# core-feather-shield-adc-imu-advanced_v1_.net
KiCad netlist of a schematic drawn in EAGLE
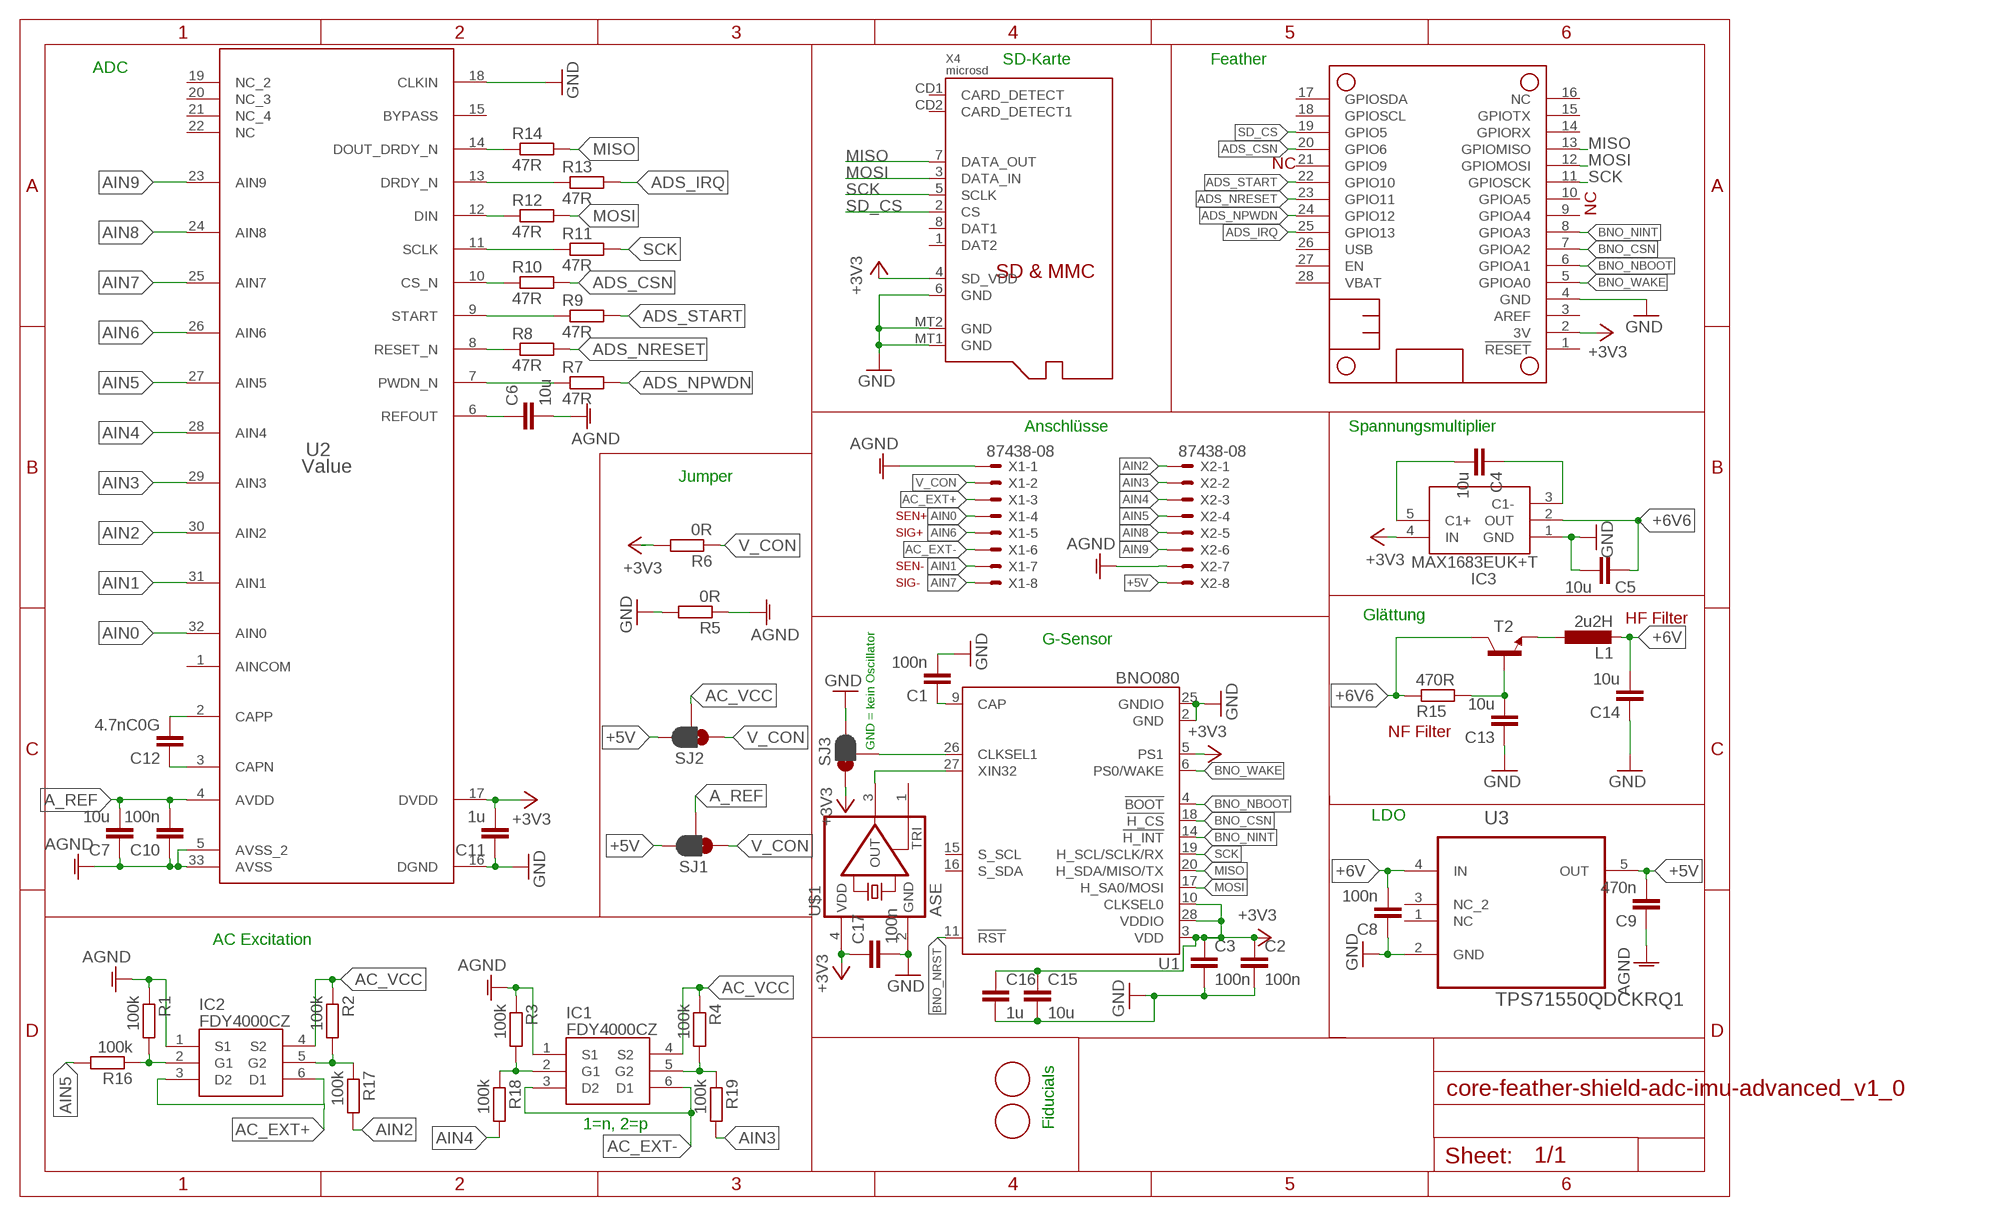
[diagram p0: schematic, sheet 1]

(export (version "E")
  (design (tool "Eeschema 10.0.6"))
  (components
    (comp (ref "C1")
      (value "100n")
      (footprint "eagle-import:C0805")
      (libsource (lib "eagle-import") (part "C-EUC0805"))
    )
    (comp (ref "C2")
      (value "100n")
      (footprint "eagle-import:C0805")
      (libsource (lib "eagle-import") (part "C-EUC0805"))
    )
    (comp (ref "C3")
      (value "100n")
      (footprint "eagle-import:C0805")
      (libsource (lib "eagle-import") (part "C-EUC0805"))
    )
    (comp (ref "C4")
      (value "10u")
      (footprint "eagle-import:C0805")
      (libsource (lib "eagle-import") (part "C-EUC0805"))
    )
    (comp (ref "C5")
      (value "10u")
      (footprint "eagle-import:C0805")
      (libsource (lib "eagle-import") (part "C-EUC0805"))
    )
    (comp (ref "C6")
      (value "10u")
      (footprint "eagle-import:C0805")
      (libsource (lib "eagle-import") (part "C-EUC0805"))
    )
    (comp (ref "C7")
      (value "10u")
      (footprint "eagle-import:C0805")
      (libsource (lib "eagle-import") (part "C-EUC0805"))
    )
    (comp (ref "C8")
      (value "100n")
      (footprint "eagle-import:C0805")
      (libsource (lib "eagle-import") (part "C-EUC0805"))
    )
    (comp (ref "C9")
      (value "470n")
      (footprint "eagle-import:C0805")
      (libsource (lib "eagle-import") (part "C-EUC0805"))
    )
    (comp (ref "C10")
      (value "100n")
      (footprint "eagle-import:C0805")
      (libsource (lib "eagle-import") (part "C-EUC0805"))
    )
    (comp (ref "C11")
      (value "1u")
      (footprint "eagle-import:C0805")
      (libsource (lib "eagle-import") (part "C-EUC0805"))
    )
    (comp (ref "C12")
      (value "4.7nC0G")
      (footprint "eagle-import:C0805")
      (libsource (lib "eagle-import") (part "C-EUC0805"))
    )
    (comp (ref "C13")
      (value "10u")
      (footprint "eagle-import:C0805")
      (libsource (lib "eagle-import") (part "C-EUC0805"))
    )
    (comp (ref "C14")
      (value "10u")
      (footprint "eagle-import:C0805")
      (libsource (lib "eagle-import") (part "C-EUC0805"))
    )
    (comp (ref "C15")
      (value "10u")
      (footprint "eagle-import:C0805")
      (libsource (lib "eagle-import") (part "C-EUC0805"))
    )
    (comp (ref "C16")
      (value "1u")
      (footprint "eagle-import:C0805")
      (libsource (lib "eagle-import") (part "C-EUC0805"))
    )
    (comp (ref "C17")
      (value "100n")
      (footprint "eagle-import:C0805")
      (libsource (lib "eagle-import") (part "C-EUC0805"))
    )
    (comp (ref "IC1")
      (value "FDY4000CZ")
      (footprint "eagle-import:SOTFL50P160X60-6N")
      (fields (field (name "MOUSER_PART_NUMBER") "512-FDY4000CZ") (field (name "RS_PART_NUMBER") "6710857"))
      (libsource (lib "eagle-import") (part "FDY4000CZ"))
    )
    (comp (ref "IC2")
      (value "FDY4000CZ")
      (footprint "eagle-import:SOTFL50P160X60-6N")
      (fields (field (name "MOUSER_PART_NUMBER") "512-FDY4000CZ") (field (name "RS_PART_NUMBER") "6710857"))
      (libsource (lib "eagle-import") (part "FDY4000CZ"))
    )
    (comp (ref "IC3")
      (value "MAX1683EUK+T")
      (footprint "eagle-import:SOT95P280X145-5N")
      (fields (field (name "MOUSER_PART_NUMBER") "700-MAX1683EUKT"))
      (libsource (lib "eagle-import") (part "MAX1683EUK+T"))
    )
    (comp (ref "L1")
      (value "2u2H")
      (footprint "eagle-import:L0805")
      (libsource (lib "eagle-import") (part "L-EUL0805"))
    )
    (comp (ref "MS1")
      (value "FEATHERWING")
      (footprint "eagle-import:FEATHERWING")
      (libsource (lib "eagle-import") (part "FEATHERWING"))
    )
    (comp (ref "R1")
      (value "100k")
      (footprint "eagle-import:R0805")
      (libsource (lib "eagle-import") (part "R-EU_R0805"))
    )
    (comp (ref "R2")
      (value "100k")
      (footprint "eagle-import:R0805")
      (libsource (lib "eagle-import") (part "R-EU_R0805"))
    )
    (comp (ref "R3")
      (value "100k")
      (footprint "eagle-import:R0805")
      (libsource (lib "eagle-import") (part "R-EU_R0805"))
    )
    (comp (ref "R4")
      (value "100k")
      (footprint "eagle-import:R0805")
      (libsource (lib "eagle-import") (part "R-EU_R0805"))
    )
    (comp (ref "R5")
      (value "0R")
      (footprint "eagle-import:R0805")
      (libsource (lib "eagle-import") (part "R-EU_R0805"))
    )
    (comp (ref "R6")
      (value "0R")
      (footprint "eagle-import:R0805")
      (libsource (lib "eagle-import") (part "R-EU_R0805"))
    )
    (comp (ref "R7")
      (value "47R")
      (footprint "eagle-import:R0805")
      (libsource (lib "eagle-import") (part "R-EU_R0805"))
    )
    (comp (ref "R8")
      (value "47R")
      (footprint "eagle-import:R0805")
      (libsource (lib "eagle-import") (part "R-EU_R0805"))
    )
    (comp (ref "R9")
      (value "47R")
      (footprint "eagle-import:R0805")
      (libsource (lib "eagle-import") (part "R-EU_R0805"))
    )
    (comp (ref "R10")
      (value "47R")
      (footprint "eagle-import:R0805")
      (libsource (lib "eagle-import") (part "R-EU_R0805"))
    )
    (comp (ref "R11")
      (value "47R")
      (footprint "eagle-import:R0805")
      (libsource (lib "eagle-import") (part "R-EU_R0805"))
    )
    (comp (ref "R12")
      (value "47R")
      (footprint "eagle-import:R0805")
      (libsource (lib "eagle-import") (part "R-EU_R0805"))
    )
    (comp (ref "R13")
      (value "47R")
      (footprint "eagle-import:R0805")
      (libsource (lib "eagle-import") (part "R-EU_R0805"))
    )
    (comp (ref "R14")
      (value "47R")
      (footprint "eagle-import:R0805")
      (libsource (lib "eagle-import") (part "R-EU_R0805"))
    )
    (comp (ref "R15")
      (value "470R")
      (footprint "eagle-import:R0805")
      (libsource (lib "eagle-import") (part "R-EU_R0805"))
    )
    (comp (ref "R16")
      (value "100k")
      (footprint "eagle-import:R0805")
      (libsource (lib "eagle-import") (part "R-EU_R0805"))
    )
    (comp (ref "R17")
      (value "100k")
      (footprint "eagle-import:R0805")
      (libsource (lib "eagle-import") (part "R-EU_R0805"))
    )
    (comp (ref "R18")
      (value "100k")
      (footprint "eagle-import:R0805")
      (libsource (lib "eagle-import") (part "R-EU_R0805"))
    )
    (comp (ref "R19")
      (value "100k")
      (footprint "eagle-import:R0805")
      (libsource (lib "eagle-import") (part "R-EU_R0805"))
    )
    (comp (ref "SJ1")
      (value "JUMPER_PAD-3-1&2_NC_BY_PASTE")
      (footprint "eagle-import:PAD-HUMPER-3-1&2_NC_BY_PASTE_YES_SILK_FULL_BOX")
      (libsource (lib "eagle-import") (part "JUMPER_PAD-3-1&2_NC_BY_PASTE"))
    )
    (comp (ref "SJ2")
      (value "JUMPER_PAD-3-1&2_NC_BY_PASTE")
      (footprint "eagle-import:PAD-HUMPER-3-1&2_NC_BY_PASTE_YES_SILK_FULL_BOX")
      (libsource (lib "eagle-import") (part "JUMPER_PAD-3-1&2_NC_BY_PASTE"))
    )
    (comp (ref "SJ3")
      (value "JUMPER_PAD-3-1&2_NC_BY_PASTE")
      (footprint "eagle-import:PAD-HUMPER-3-1&2_NC_BY_PASTE_YES_SILK_FULL_BOX")
      (libsource (lib "eagle-import") (part "JUMPER_PAD-3-1&2_NC_BY_PASTE"))
    )
    (comp (ref "T2")
      (value "BC808-NPN-SOT23-BEC")
      (footprint "eagle-import:SOT23-BEC")
      (libsource (lib "eagle-import") (part "-NPN-SOT23-BECBC808"))
    )
    (comp (ref "U$1")
      (value "ASE")
      (footprint "eagle-import:ASE")
      (libsource (lib "eagle-import") (part "ASE"))
    )
    (comp (ref "U$8")
      (value "FIDUCIAL")
      (footprint "eagle-import:FIDUCIAL_1MM")
      (libsource (lib "eagle-import") (part "FIDUCIAL"))
    )
    (comp (ref "U$9")
      (value "FIDUCIAL")
      (footprint "eagle-import:FIDUCIAL_1MM")
      (libsource (lib "eagle-import") (part "FIDUCIAL"))
    )
    (comp (ref "U1")
      (value "BNO080")
      (footprint "eagle-import:LGA-28")
      (fields (field (name "MF") "Hillcrest Laboratories,"))
      (libsource (lib "eagle-import") (part "BNO080"))
    )
    (comp (ref "U2")
      (value "Value")
      (footprint "eagle-import:RHB0032E")
      (fields (field (name "MANUFACTURER") "Texas Instruments") (field (name "PARTNUMBER") "ADS1261IRHBR"))
      (libsource (lib "eagle-import") (part "ADS1261IRHBR"))
    )
    (comp (ref "U3")
      (value "TPS71550QDCKRQ1")
      (footprint "eagle-import:SOT65P210X110-5N")
      (fields (field (name "MF") "Texas Instruments"))
      (libsource (lib "eagle-import") (part "TPS71550QDCKRQ1"))
    )
    (comp (ref "X1")
      (value "87438-08")
      (footprint "eagle-import:87438-08")
      (fields (field (name "MF") "MOLEX") (field (name "SPICEPREFIX") "X"))
      (libsource (lib "eagle-import") (part "87438-08"))
    )
    (comp (ref "X2")
      (value "87438-08")
      (footprint "eagle-import:87438-08")
      (fields (field (name "MF") "MOLEX") (field (name "SPICEPREFIX") "X"))
      (libsource (lib "eagle-import") (part "87438-08"))
    )
    (comp (ref "X4")
      (value "microsd")
      (footprint "eagle-import:MICROSD")
      (libsource (lib "eagle-import") (part "MICROSD"))
    )
  )
  (nets
    (net (code "1") (name "+3V3") (class "Default")
      (node (ref "C11") (pin "2") (pinfunction "2_2") (pintype "passive"))
      (node (ref "C15") (pin "1") (pinfunction "1_1") (pintype "passive"))
      (node (ref "C16") (pin "1") (pinfunction "1_1") (pintype "passive"))
      (node (ref "C17") (pin "1") (pinfunction "1_1") (pintype "passive"))
      (node (ref "C2") (pin "1") (pinfunction "1_1") (pintype "passive"))
      (node (ref "C3") (pin "1") (pinfunction "1_1") (pintype "passive"))
      (node (ref "IC3") (pin "4") (pinfunction "IN_4") (pintype "input"))
      (node (ref "MS1") (pin "2") (pinfunction "3V_2") (pintype "power_in"))
      (node (ref "R6") (pin "2") (pinfunction "2_2") (pintype "passive"))
      (node (ref "SJ3") (pin "3") (pinfunction "3_3") (pintype "passive"))
      (node (ref "U$1") (pin "4") (pinfunction "VDD_4") (pintype "power_in"))
      (node (ref "U1") (pin "10") (pinfunction "CLKSEL0_10") (pintype "bidirectional"))
      (node (ref "U1") (pin "28") (pinfunction "VDDIO_28") (pintype "bidirectional"))
      (node (ref "U1") (pin "3") (pinfunction "VDD_3") (pintype "bidirectional"))
      (node (ref "U1") (pin "5") (pinfunction "PS1_5") (pintype "bidirectional"))
      (node (ref "U2") (pin "17") (pinfunction "DVDD_17") (pintype "power_in"))
      (node (ref "X4") (pin "4") (pinfunction "SD_VDD_4") (pintype "power_in"))
    )
    (net (code "2") (name "+5V") (class "Default")
      (node (ref "C9") (pin "2") (pinfunction "2_2") (pintype "passive"))
      (node (ref "SJ1") (pin "1") (pinfunction "1_1") (pintype "passive"))
      (node (ref "SJ2") (pin "1") (pinfunction "1_1") (pintype "passive"))
      (node (ref "U3") (pin "5") (pinfunction "OUT_5") (pintype "output"))
      (node (ref "X2") (pin "8") (pinfunction "S_8") (pintype "passive"))
    )
    (net (code "3") (name "+6V") (class "Default")
      (node (ref "C14") (pin "2") (pinfunction "2_2") (pintype "passive"))
      (node (ref "C8") (pin "2") (pinfunction "2_2") (pintype "passive"))
      (node (ref "L1") (pin "2") (pinfunction "2_2") (pintype "passive"))
      (node (ref "U3") (pin "4") (pinfunction "IN_4") (pintype "power_in"))
    )
    (net (code "4") (name "+6V6") (class "Default")
      (node (ref "C5") (pin "1") (pinfunction "1_1") (pintype "passive"))
      (node (ref "IC3") (pin "2") (pinfunction "OUT_2") (pintype "output"))
      (node (ref "R15") (pin "2") (pinfunction "2_2") (pintype "passive"))
      (node (ref "T2") (pin "C") (pinfunction "C_C") (pintype "passive"))
    )
    (net (code "5") (name "/USB") (class "Default")
      (node (ref "MS1") (pin "26") (pinfunction "USB_26") (pintype "power_in"))
    )
    (net (code "6") (name "/VBAT") (class "Default")
      (node (ref "MS1") (pin "28") (pinfunction "VBAT_28") (pintype "power_in"))
    )
    (net (code "7") (name "AC_EXT+") (class "Default")
      (node (ref "IC2") (pin "3") (pinfunction "D2_3") (pintype "bidirectional"))
      (node (ref "IC2") (pin "6") (pinfunction "D1_6") (pintype "bidirectional"))
      (node (ref "X1") (pin "3") (pinfunction "S_3") (pintype "passive"))
    )
    (net (code "8") (name "AC_EXT-") (class "Default")
      (node (ref "IC1") (pin "3") (pinfunction "D2_3") (pintype "bidirectional"))
      (node (ref "IC1") (pin "6") (pinfunction "D1_6") (pintype "bidirectional"))
      (node (ref "X1") (pin "6") (pinfunction "S_6") (pintype "passive"))
    )
    (net (code "9") (name "AC_VCC") (class "Default")
      (node (ref "IC1") (pin "4") (pinfunction "S2_4") (pintype "bidirectional"))
      (node (ref "IC2") (pin "4") (pinfunction "S2_4") (pintype "bidirectional"))
      (node (ref "R2") (pin "1") (pinfunction "1_1") (pintype "passive"))
      (node (ref "R4") (pin "1") (pinfunction "1_1") (pintype "passive"))
      (node (ref "SJ2") (pin "2") (pinfunction "2_2") (pintype "passive"))
    )
    (net (code "10") (name "ADS_CSN") (class "Default")
      (node (ref "MS1") (pin "20") (pinfunction "GPIO6_20") (pintype "bidirectional"))
      (node (ref "R10") (pin "2") (pinfunction "2_2") (pintype "passive"))
    )
    (net (code "11") (name "ADS_IRQ") (class "Default")
      (node (ref "MS1") (pin "25") (pinfunction "GPIO13_25") (pintype "bidirectional"))
      (node (ref "R13") (pin "2") (pinfunction "2_2") (pintype "passive"))
    )
    (net (code "12") (name "ADS_NPWDN") (class "Default")
      (node (ref "MS1") (pin "24") (pinfunction "GPIO12_24") (pintype "bidirectional"))
      (node (ref "R7") (pin "2") (pinfunction "2_2") (pintype "passive"))
    )
    (net (code "13") (name "ADS_NRESET") (class "Default")
      (node (ref "MS1") (pin "23") (pinfunction "GPIO11_23") (pintype "bidirectional"))
      (node (ref "R8") (pin "2") (pinfunction "2_2") (pintype "passive"))
    )
    (net (code "14") (name "ADS_START") (class "Default")
      (node (ref "MS1") (pin "22") (pinfunction "GPIO10_22") (pintype "bidirectional"))
      (node (ref "R9") (pin "2") (pinfunction "2_2") (pintype "passive"))
    )
    (net (code "15") (name "AGND") (class "Default")
      (node (ref "C10") (pin "1") (pinfunction "1_1") (pintype "passive"))
      (node (ref "C6") (pin "2") (pinfunction "2_2") (pintype "passive"))
      (node (ref "C7") (pin "1") (pinfunction "1_1") (pintype "passive"))
      (node (ref "C9") (pin "1") (pinfunction "1_1") (pintype "passive"))
      (node (ref "IC1") (pin "1") (pinfunction "S1_1") (pintype "bidirectional"))
      (node (ref "IC2") (pin "1") (pinfunction "S1_1") (pintype "bidirectional"))
      (node (ref "R1") (pin "1") (pinfunction "1_1") (pintype "passive"))
      (node (ref "R3") (pin "1") (pinfunction "1_1") (pintype "passive"))
      (node (ref "R5") (pin "1") (pinfunction "1_1") (pintype "passive"))
      (node (ref "U2") (pin "33") (pinfunction "AVSS_33") (pintype "power_in"))
      (node (ref "U2") (pin "5") (pinfunction "AVSS_2_5") (pintype "power_in"))
      (node (ref "X1") (pin "1") (pinfunction "S_1") (pintype "passive"))
      (node (ref "X2") (pin "7") (pinfunction "S_7") (pintype "passive"))
    )
    (net (code "16") (name "AIN0") (class "Default")
      (node (ref "U2") (pin "32") (pinfunction "AIN0_32") (pintype "input"))
      (node (ref "X1") (pin "4") (pinfunction "S_4") (pintype "passive"))
    )
    (net (code "17") (name "AIN1") (class "Default")
      (node (ref "U2") (pin "31") (pinfunction "AIN1_31") (pintype "input"))
      (node (ref "X1") (pin "7") (pinfunction "S_7") (pintype "passive"))
    )
    (net (code "18") (name "AIN2") (class "Default")
      (node (ref "R17") (pin "2") (pinfunction "2_2") (pintype "passive"))
      (node (ref "U2") (pin "30") (pinfunction "AIN2_30") (pintype "input"))
      (node (ref "X2") (pin "1") (pinfunction "S_1") (pintype "passive"))
    )
    (net (code "19") (name "AIN3") (class "Default")
      (node (ref "R19") (pin "2") (pinfunction "2_2") (pintype "passive"))
      (node (ref "U2") (pin "29") (pinfunction "AIN3_29") (pintype "input"))
      (node (ref "X2") (pin "2") (pinfunction "S_2") (pintype "passive"))
    )
    (net (code "20") (name "AIN4") (class "Default")
      (node (ref "R18") (pin "2") (pinfunction "2_2") (pintype "passive"))
      (node (ref "U2") (pin "28") (pinfunction "AIN4_28") (pintype "input"))
      (node (ref "X2") (pin "3") (pinfunction "S_3") (pintype "passive"))
    )
    (net (code "21") (name "AIN5") (class "Default")
      (node (ref "R16") (pin "2") (pinfunction "2_2") (pintype "passive"))
      (node (ref "U2") (pin "27") (pinfunction "AIN5_27") (pintype "input"))
      (node (ref "X2") (pin "4") (pinfunction "S_4") (pintype "passive"))
    )
    (net (code "22") (name "AIN6") (class "Default")
      (node (ref "U2") (pin "26") (pinfunction "AIN6_26") (pintype "input"))
      (node (ref "X1") (pin "5") (pinfunction "S_5") (pintype "passive"))
    )
    (net (code "23") (name "AIN7") (class "Default")
      (node (ref "U2") (pin "25") (pinfunction "AIN7_25") (pintype "input"))
      (node (ref "X1") (pin "8") (pinfunction "S_8") (pintype "passive"))
    )
    (net (code "24") (name "AIN8") (class "Default")
      (node (ref "U2") (pin "24") (pinfunction "AIN8_24") (pintype "input"))
      (node (ref "X2") (pin "5") (pinfunction "S_5") (pintype "passive"))
    )
    (net (code "25") (name "AIN9") (class "Default")
      (node (ref "U2") (pin "23") (pinfunction "AIN9_23") (pintype "input"))
      (node (ref "X2") (pin "6") (pinfunction "S_6") (pintype "passive"))
    )
    (net (code "26") (name "A_REF") (class "Default")
      (node (ref "C10") (pin "2") (pinfunction "2_2") (pintype "passive"))
      (node (ref "C7") (pin "2") (pinfunction "2_2") (pintype "passive"))
      (node (ref "SJ1") (pin "2") (pinfunction "2_2") (pintype "passive"))
      (node (ref "U2") (pin "4") (pinfunction "AVDD_4") (pintype "power_in"))
    )
    (net (code "27") (name "BNO_CSN") (class "Default")
      (node (ref "MS1") (pin "7") (pinfunction "GPIOA2_7") (pintype "bidirectional"))
      (node (ref "U1") (pin "18") (pinfunction "~{H_CS}_18") (pintype "bidirectional"))
    )
    (net (code "28") (name "BNO_NBOOT") (class "Default")
      (node (ref "MS1") (pin "6") (pinfunction "GPIOA1_6") (pintype "bidirectional"))
      (node (ref "U1") (pin "4") (pinfunction "~{BOOT}_4") (pintype "bidirectional"))
    )
    (net (code "29") (name "BNO_NINT") (class "Default")
      (node (ref "MS1") (pin "8") (pinfunction "GPIOA3_8") (pintype "bidirectional"))
      (node (ref "U1") (pin "14") (pinfunction "~{H_INT}_14") (pintype "bidirectional"))
    )
    (net (code "30") (name "BNO_NRST") (class "Default")
      (node (ref "U1") (pin "11") (pinfunction "~{RST}_11") (pintype "bidirectional"))
    )
    (net (code "31") (name "BNO_WAKE") (class "Default")
      (node (ref "MS1") (pin "5") (pinfunction "GPIOA0_5") (pintype "bidirectional"))
      (node (ref "U1") (pin "6") (pinfunction "PS0/WAKE_6") (pintype "bidirectional"))
    )
    (net (code "32") (name "GND") (class "Default")
      (node (ref "C1") (pin "2") (pinfunction "2_2") (pintype "passive"))
      (node (ref "C11") (pin "1") (pinfunction "1_1") (pintype "passive"))
      (node (ref "C13") (pin "1") (pinfunction "1_1") (pintype "passive"))
      (node (ref "C14") (pin "1") (pinfunction "1_1") (pintype "passive"))
      (node (ref "C15") (pin "2") (pinfunction "2_2") (pintype "passive"))
      (node (ref "C16") (pin "2") (pinfunction "2_2") (pintype "passive"))
      (node (ref "C17") (pin "2") (pinfunction "2_2") (pintype "passive"))
      (node (ref "C2") (pin "2") (pinfunction "2_2") (pintype "passive"))
      (node (ref "C3") (pin "2") (pinfunction "2_2") (pintype "passive"))
      (node (ref "C5") (pin "2") (pinfunction "2_2") (pintype "passive"))
      (node (ref "C8") (pin "1") (pinfunction "1_1") (pintype "passive"))
      (node (ref "IC3") (pin "1") (pinfunction "GND_1") (pintype "power_in"))
      (node (ref "MS1") (pin "4") (pinfunction "GND_4") (pintype "power_in"))
      (node (ref "R5") (pin "2") (pinfunction "2_2") (pintype "passive"))
      (node (ref "SJ3") (pin "1") (pinfunction "1_1") (pintype "passive"))
      (node (ref "U$1") (pin "2") (pinfunction "GND_2") (pintype "power_in"))
      (node (ref "U1") (pin "2") (pinfunction "GND_2") (pintype "bidirectional"))
      (node (ref "U1") (pin "25") (pinfunction "GNDIO_25") (pintype "bidirectional"))
      (node (ref "U2") (pin "16") (pinfunction "DGND_16") (pintype "power_in"))
      (node (ref "U2") (pin "18") (pinfunction "CLKIN_18") (pintype "input"))
      (node (ref "U3") (pin "2") (pinfunction "GND_2") (pintype "passive"))
      (node (ref "X4") (pin "6") (pinfunction "GND_6") (pintype "power_in"))
      (node (ref "X4") (pin "MT1") (pinfunction "GND_MT1") (pintype "power_in"))
      (node (ref "X4") (pin "MT2") (pinfunction "GND_MT2") (pintype "power_in"))
    )
    (net (code "33") (name "MISO") (class "Default")
      (node (ref "MS1") (pin "13") (pinfunction "GPIOMISO_13") (pintype "bidirectional"))
      (node (ref "R14") (pin "2") (pinfunction "2_2") (pintype "passive"))
      (node (ref "U1") (pin "20") (pinfunction "H_SDA/MISO/TX_20") (pintype "bidirectional"))
      (node (ref "X4") (pin "7") (pinfunction "DATA_OUT_7") (pintype "output"))
    )
    (net (code "34") (name "MOSI") (class "Default")
      (node (ref "MS1") (pin "12") (pinfunction "GPIOMOSI_12") (pintype "bidirectional"))
      (node (ref "R12") (pin "2") (pinfunction "2_2") (pintype "passive"))
      (node (ref "U1") (pin "17") (pinfunction "H_SA0/MOSI_17") (pintype "bidirectional"))
      (node (ref "X4") (pin "3") (pinfunction "DATA_IN_3") (pintype "input"))
    )
    (net (code "35") (name "Net-(C13-Pad2)") (class "Default")
      (node (ref "C13") (pin "2") (pinfunction "2_2") (pintype "passive"))
      (node (ref "R15") (pin "1") (pinfunction "1_1") (pintype "passive"))
      (node (ref "T2") (pin "B") (pinfunction "B_B") (pintype "passive"))
    )
    (net (code "36") (name "Net-(IC1-G1)") (class "Default")
      (node (ref "IC1") (pin "2") (pinfunction "G1_2") (pintype "bidirectional"))
      (node (ref "R18") (pin "1") (pinfunction "1_1") (pintype "passive"))
      (node (ref "R3") (pin "2") (pinfunction "2_2") (pintype "passive"))
    )
    (net (code "37") (name "Net-(IC1-G2)") (class "Default")
      (node (ref "IC1") (pin "5") (pinfunction "G2_5") (pintype "bidirectional"))
      (node (ref "R19") (pin "1") (pinfunction "1_1") (pintype "passive"))
      (node (ref "R4") (pin "2") (pinfunction "2_2") (pintype "passive"))
    )
    (net (code "38") (name "Net-(IC2-G1)") (class "Default")
      (node (ref "IC2") (pin "2") (pinfunction "G1_2") (pintype "bidirectional"))
      (node (ref "R1") (pin "2") (pinfunction "2_2") (pintype "passive"))
      (node (ref "R16") (pin "1") (pinfunction "1_1") (pintype "passive"))
    )
    (net (code "39") (name "Net-(IC2-G2)") (class "Default")
      (node (ref "IC2") (pin "5") (pinfunction "G2_5") (pintype "bidirectional"))
      (node (ref "R17") (pin "1") (pinfunction "1_1") (pintype "passive"))
      (node (ref "R2") (pin "2") (pinfunction "2_2") (pintype "passive"))
    )
    (net (code "40") (name "Net-(IC3-C1+)") (class "Default")
      (node (ref "C4") (pin "2") (pinfunction "2_2") (pintype "passive"))
      (node (ref "IC3") (pin "5") (pinfunction "C1+_5") (pintype "bidirectional"))
    )
    (net (code "41") (name "Net-(IC3-C1-)") (class "Default")
      (node (ref "C4") (pin "1") (pinfunction "1_1") (pintype "passive"))
      (node (ref "IC3") (pin "3") (pinfunction "C1-_3") (pintype "bidirectional"))
    )
    (net (code "42") (name "Net-(L1-Pad1)") (class "Default")
      (node (ref "L1") (pin "1") (pinfunction "1_1") (pintype "passive"))
      (node (ref "T2") (pin "E") (pinfunction "E_E") (pintype "passive"))
    )
    (net (code "43") (name "Net-(U$1-OUT)") (class "Default")
      (node (ref "U$1") (pin "3") (pinfunction "OUT_3") (pintype "output"))
      (node (ref "U1") (pin "27") (pinfunction "XIN32_27") (pintype "bidirectional"))
    )
    (net (code "44") (name "Net-(U1-CAP)") (class "Default")
      (node (ref "C1") (pin "1") (pinfunction "1_1") (pintype "passive"))
      (node (ref "U1") (pin "9") (pinfunction "CAP_9") (pintype "bidirectional"))
    )
    (net (code "45") (name "Net-(U1-CLKSEL1)") (class "Default")
      (node (ref "SJ3") (pin "2") (pinfunction "2_2") (pintype "passive"))
      (node (ref "U1") (pin "26") (pinfunction "CLKSEL1_26") (pintype "bidirectional"))
    )
    (net (code "46") (name "Net-(U2-CAPN)") (class "Default")
      (node (ref "C12") (pin "1") (pinfunction "1_1") (pintype "passive"))
      (node (ref "U2") (pin "3") (pinfunction "CAPN_3") (pintype "passive"))
    )
    (net (code "47") (name "Net-(U2-CAPP)") (class "Default")
      (node (ref "C12") (pin "2") (pinfunction "2_2") (pintype "passive"))
      (node (ref "U2") (pin "2") (pinfunction "CAPP_2") (pintype "passive"))
    )
    (net (code "48") (name "Net-(U2-CS_N)") (class "Default")
      (node (ref "R10") (pin "1") (pinfunction "1_1") (pintype "passive"))
      (node (ref "U2") (pin "10") (pinfunction "CS_N_10") (pintype "input"))
    )
    (net (code "49") (name "Net-(U2-DIN)") (class "Default")
      (node (ref "R12") (pin "1") (pinfunction "1_1") (pintype "passive"))
      (node (ref "U2") (pin "12") (pinfunction "DIN_12") (pintype "input"))
    )
    (net (code "50") (name "Net-(U2-DOUT_DRDY_N)") (class "Default")
      (node (ref "R14") (pin "1") (pinfunction "1_1") (pintype "passive"))
      (node (ref "U2") (pin "14") (pinfunction "DOUT_DRDY_N_14") (pintype "output"))
    )
    (net (code "51") (name "Net-(U2-DRDY_N)") (class "Default")
      (node (ref "R13") (pin "1") (pinfunction "1_1") (pintype "passive"))
      (node (ref "U2") (pin "13") (pinfunction "DRDY_N_13") (pintype "output"))
    )
    (net (code "52") (name "Net-(U2-PWDN_N)") (class "Default")
      (node (ref "R7") (pin "1") (pinfunction "1_1") (pintype "passive"))
      (node (ref "U2") (pin "7") (pinfunction "PWDN_N_7") (pintype "input"))
    )
    (net (code "53") (name "Net-(U2-REFOUT)") (class "Default")
      (node (ref "C6") (pin "1") (pinfunction "1_1") (pintype "passive"))
      (node (ref "U2") (pin "6") (pinfunction "REFOUT_6") (pintype "output"))
    )
    (net (code "54") (name "Net-(U2-RESET_N)") (class "Default")
      (node (ref "R8") (pin "1") (pinfunction "1_1") (pintype "passive"))
      (node (ref "U2") (pin "8") (pinfunction "RESET_N_8") (pintype "input"))
    )
    (net (code "55") (name "Net-(U2-SCLK)") (class "Default")
      (node (ref "R11") (pin "1") (pinfunction "1_1") (pintype "passive"))
      (node (ref "U2") (pin "11") (pinfunction "SCLK_11") (pintype "input"))
    )
    (net (code "56") (name "Net-(U2-START)") (class "Default")
      (node (ref "R9") (pin "1") (pinfunction "1_1") (pintype "passive"))
      (node (ref "U2") (pin "9") (pinfunction "START_9") (pintype "input"))
    )
    (net (code "57") (name "SCK") (class "Default")
      (node (ref "MS1") (pin "11") (pinfunction "GPIOSCK_11") (pintype "bidirectional"))
      (node (ref "R11") (pin "2") (pinfunction "2_2") (pintype "passive"))
      (node (ref "U1") (pin "19") (pinfunction "H_SCL/SCLK/RX_19") (pintype "bidirectional"))
      (node (ref "X4") (pin "5") (pinfunction "SCLK_5") (pintype "input"))
    )
    (net (code "58") (name "SD_CS") (class "Default")
      (node (ref "MS1") (pin "19") (pinfunction "GPIO5_19") (pintype "bidirectional"))
      (node (ref "X4") (pin "2") (pinfunction "CS_2") (pintype "input"))
    )
    (net (code "59") (name "V_CON") (class "Default")
      (node (ref "R6") (pin "1") (pinfunction "1_1") (pintype "passive"))
      (node (ref "SJ1") (pin "3") (pinfunction "3_3") (pintype "passive"))
      (node (ref "SJ2") (pin "3") (pinfunction "3_3") (pintype "passive"))
      (node (ref "X1") (pin "2") (pinfunction "S_2") (pintype "passive"))
    )
    (net (code "60") (name "unconnected-(MS1-AREF-Pad3)") (class "Default")
      (node (ref "MS1") (pin "3") (pinfunction "AREF_3") (pintype "passive"))
    )
    (net (code "61") (name "unconnected-(MS1-EN-Pad27)") (class "Default")
      (node (ref "MS1") (pin "27") (pinfunction "EN_27") (pintype "passive"))
    )
    (net (code "62") (name "unconnected-(MS1-GPIO9-Pad21)") (class "Default")
      (node (ref "MS1") (pin "21") (pinfunction "GPIO9_21") (pintype "bidirectional"))
    )
    (net (code "63") (name "unconnected-(MS1-GPIOA4-Pad9)") (class "Default")
      (node (ref "MS1") (pin "9") (pinfunction "GPIOA4_9") (pintype "bidirectional"))
    )
    (net (code "64") (name "unconnected-(MS1-GPIOA5-Pad10)") (class "Default")
      (node (ref "MS1") (pin "10") (pinfunction "GPIOA5_10") (pintype "bidirectional"))
    )
    (net (code "65") (name "unconnected-(MS1-GPIORX-Pad14)") (class "Default")
      (node (ref "MS1") (pin "14") (pinfunction "GPIORX_14") (pintype "bidirectional"))
    )
    (net (code "66") (name "unconnected-(MS1-GPIOSCL-Pad18)") (class "Default")
      (node (ref "MS1") (pin "18") (pinfunction "GPIOSCL_18") (pintype "bidirectional"))
    )
    (net (code "67") (name "unconnected-(MS1-GPIOSDA-Pad17)") (class "Default")
      (node (ref "MS1") (pin "17") (pinfunction "GPIOSDA_17") (pintype "bidirectional"))
    )
    (net (code "68") (name "unconnected-(MS1-GPIOTX-Pad15)") (class "Default")
      (node (ref "MS1") (pin "15") (pinfunction "GPIOTX_15") (pintype "bidirectional"))
    )
    (net (code "69") (name "unconnected-(MS1-NC-Pad16)") (class "Default")
      (node (ref "MS1") (pin "16") (pinfunction "NC_16") (pintype "passive"))
    )
    (net (code "70") (name "unconnected-(MS1-~{RESET}-Pad1)") (class "Default")
      (node (ref "MS1") (pin "1") (pinfunction "~{RESET}_1") (pintype "input"))
    )
    (net (code "71") (name "unconnected-(U$1-TRI-Pad1)") (class "Default")
      (node (ref "U$1") (pin "1") (pinfunction "TRI_1") (pintype "input"))
    )
    (net (code "72") (name "unconnected-(U1-S_SCL-Pad15)") (class "Default")
      (node (ref "U1") (pin "15") (pinfunction "S_SCL_15") (pintype "bidirectional"))
    )
    (net (code "73") (name "unconnected-(U1-S_SDA-Pad16)") (class "Default")
      (node (ref "U1") (pin "16") (pinfunction "S_SDA_16") (pintype "bidirectional"))
    )
    (net (code "74") (name "unconnected-(U2-AINCOM-Pad1)") (class "Default")
      (node (ref "U2") (pin "1") (pinfunction "AINCOM_1") (pintype "input"))
    )
    (net (code "75") (name "unconnected-(U2-BYPASS-Pad15)") (class "Default")
      (node (ref "U2") (pin "15") (pinfunction "BYPASS_15") (pintype "passive"))
    )
    (net (code "76") (name "unconnected-(U2-NC-Pad22)") (class "Default")
      (node (ref "U2") (pin "22") (pinfunction "NC_22") (pintype "passive"))
    )
    (net (code "77") (name "unconnected-(U2-NC_2-Pad19)") (class "Default")
      (node (ref "U2") (pin "19") (pinfunction "NC_2_19") (pintype "passive"))
    )
    (net (code "78") (name "unconnected-(U2-NC_3-Pad20)") (class "Default")
      (node (ref "U2") (pin "20") (pinfunction "NC_3_20") (pintype "passive"))
    )
    (net (code "79") (name "unconnected-(U2-NC_4-Pad21)") (class "Default")
      (node (ref "U2") (pin "21") (pinfunction "NC_4_21") (pintype "passive"))
    )
    (net (code "80") (name "unconnected-(U3-NC-Pad1)") (class "Default")
      (node (ref "U3") (pin "1") (pinfunction "NC_1") (pintype "no_connect"))
    )
    (net (code "81") (name "unconnected-(U3-NC_2-Pad3)") (class "Default")
      (node (ref "U3") (pin "3") (pinfunction "NC_2_3") (pintype "no_connect"))
    )
    (net (code "82") (name "unconnected-(X4-CARD_DETECT-PadCD1)") (class "Default")
      (node (ref "X4") (pin "CD1") (pinfunction "CARD_DETECT_CD1") (pintype "passive"))
    )
    (net (code "83") (name "unconnected-(X4-CARD_DETECT1-PadCD2)") (class "Default")
      (node (ref "X4") (pin "CD2") (pinfunction "CARD_DETECT1_CD2") (pintype "passive"))
    )
    (net (code "84") (name "unconnected-(X4-DAT1-Pad8)") (class "Default")
      (node (ref "X4") (pin "8") (pinfunction "DAT1_8") (pintype "bidirectional"))
    )
    (net (code "85") (name "unconnected-(X4-DAT2-Pad1)") (class "Default")
      (node (ref "X4") (pin "1") (pinfunction "DAT2_1") (pintype "bidirectional"))
    )
  )
)
